# BitRegister.net
KiCad netlist of a schematic drawn in EAGLE
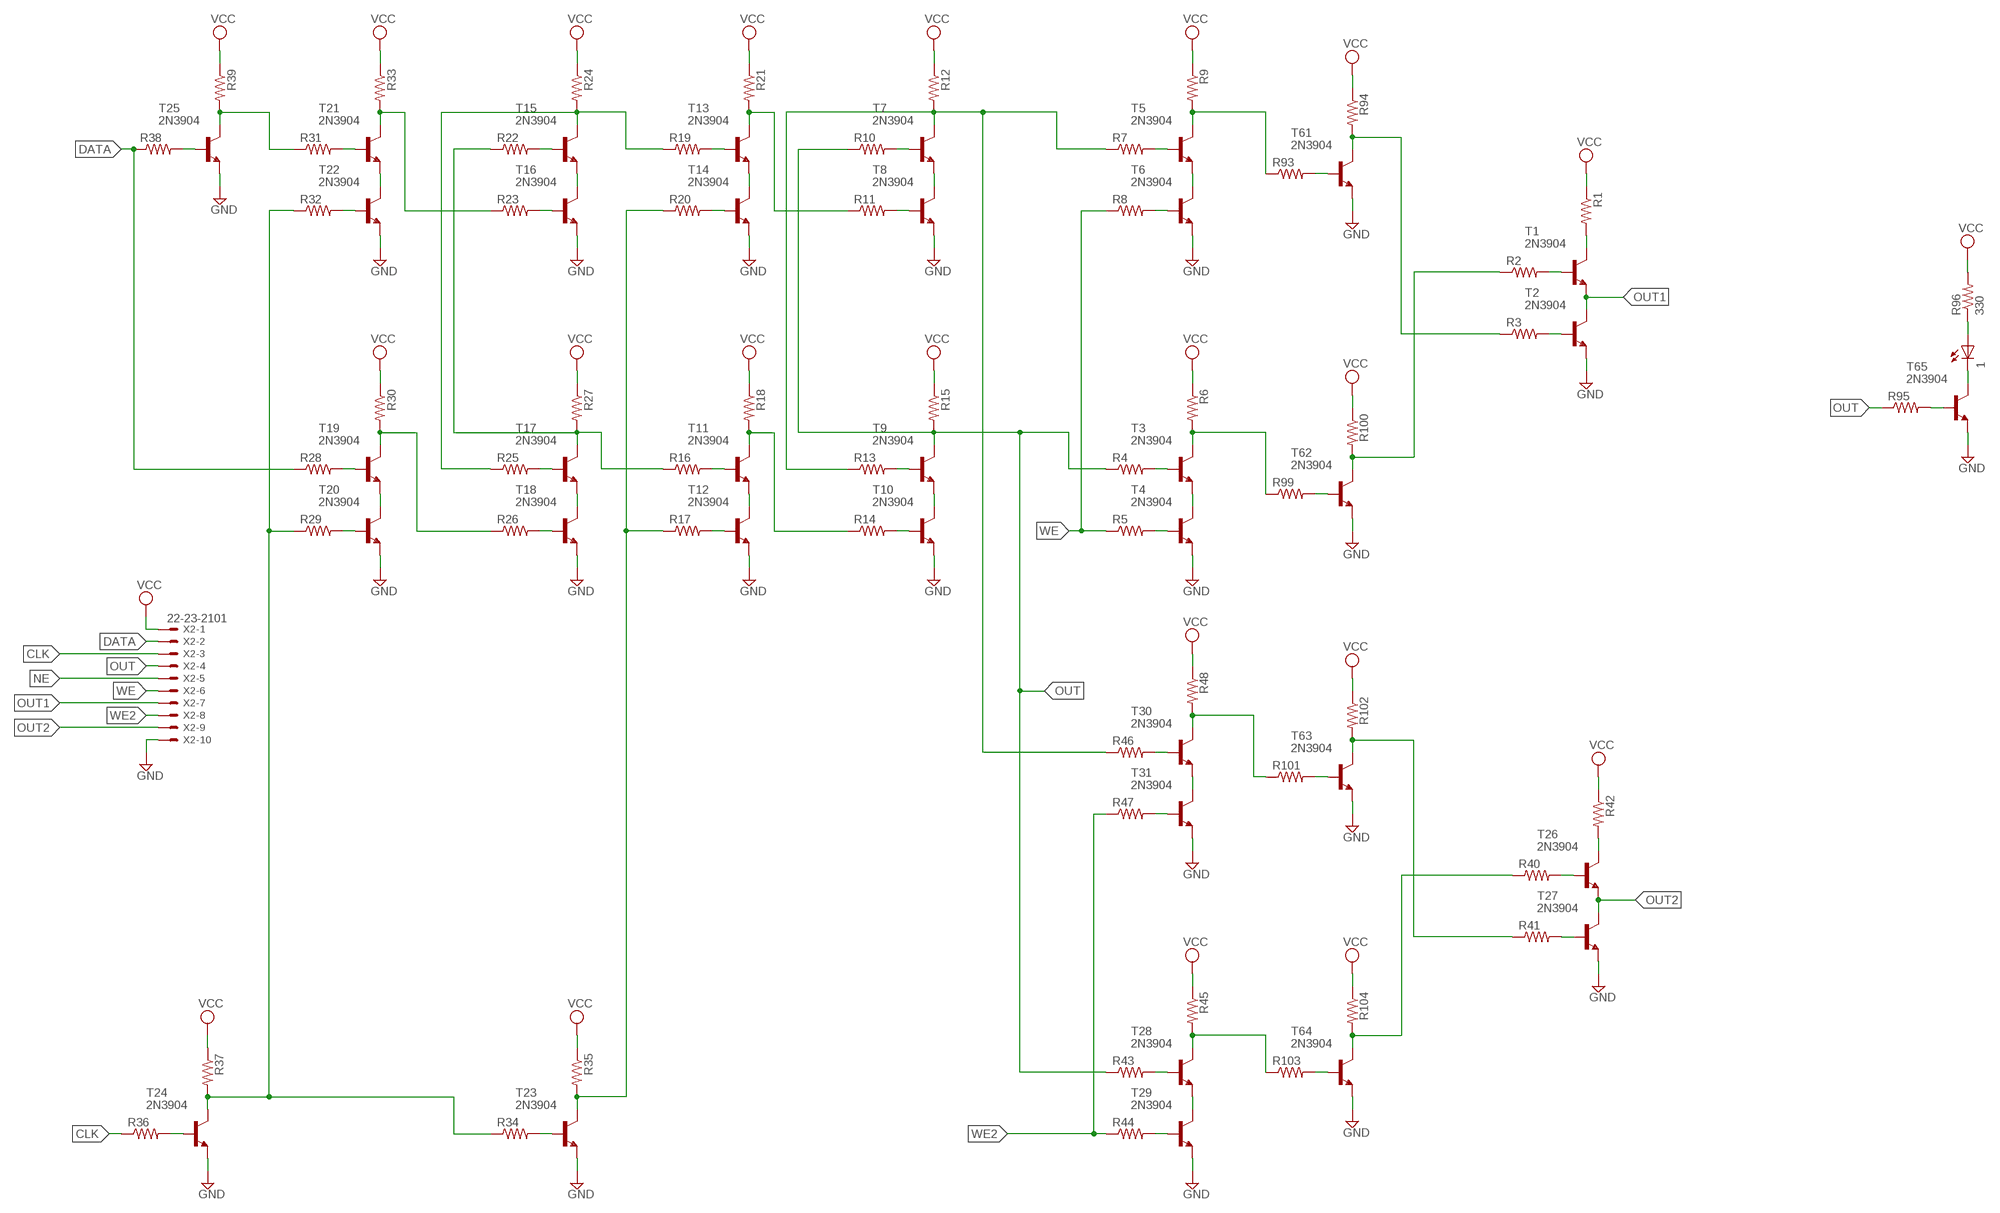
[diagram p0: schematic, sheet 1]

(export (version "E")
  (design (tool "Eeschema 10.0.6"))
  (components
    (comp (ref "1")
      (value "LED5MM")
      (footprint "eagle-import:LED5MM")
      (libsource (lib "eagle-import") (part "LED5MM"))
    )
    (comp (ref "R1")
      (value "R-US_0309/10")
      (footprint "eagle-import:0309_10")
      (libsource (lib "eagle-import") (part "R-US_0309/10"))
    )
    (comp (ref "R2")
      (value "R-US_0309/10")
      (footprint "eagle-import:0309_10")
      (libsource (lib "eagle-import") (part "R-US_0309/10"))
    )
    (comp (ref "R3")
      (value "R-US_0309/10")
      (footprint "eagle-import:0309_10")
      (libsource (lib "eagle-import") (part "R-US_0309/10"))
    )
    (comp (ref "R4")
      (value "R-US_0309/10")
      (footprint "eagle-import:0309_10")
      (libsource (lib "eagle-import") (part "R-US_0309/10"))
    )
    (comp (ref "R5")
      (value "R-US_0309/10")
      (footprint "eagle-import:0309_10")
      (libsource (lib "eagle-import") (part "R-US_0309/10"))
    )
    (comp (ref "R6")
      (value "R-US_0309/10")
      (footprint "eagle-import:0309_10")
      (libsource (lib "eagle-import") (part "R-US_0309/10"))
    )
    (comp (ref "R7")
      (value "R-US_0309/10")
      (footprint "eagle-import:0309_10")
      (libsource (lib "eagle-import") (part "R-US_0309/10"))
    )
    (comp (ref "R8")
      (value "R-US_0309/10")
      (footprint "eagle-import:0309_10")
      (libsource (lib "eagle-import") (part "R-US_0309/10"))
    )
    (comp (ref "R9")
      (value "R-US_0309/10")
      (footprint "eagle-import:0309_10")
      (libsource (lib "eagle-import") (part "R-US_0309/10"))
    )
    (comp (ref "R10")
      (value "R-US_0309/10")
      (footprint "eagle-import:0309_10")
      (libsource (lib "eagle-import") (part "R-US_0309/10"))
    )
    (comp (ref "R11")
      (value "R-US_0309/10")
      (footprint "eagle-import:0309_10")
      (libsource (lib "eagle-import") (part "R-US_0309/10"))
    )
    (comp (ref "R12")
      (value "R-US_0309/10")
      (footprint "eagle-import:0309_10")
      (libsource (lib "eagle-import") (part "R-US_0309/10"))
    )
    (comp (ref "R13")
      (value "R-US_0309/10")
      (footprint "eagle-import:0309_10")
      (libsource (lib "eagle-import") (part "R-US_0309/10"))
    )
    (comp (ref "R14")
      (value "R-US_0309/10")
      (footprint "eagle-import:0309_10")
      (libsource (lib "eagle-import") (part "R-US_0309/10"))
    )
    (comp (ref "R15")
      (value "R-US_0309/10")
      (footprint "eagle-import:0309_10")
      (libsource (lib "eagle-import") (part "R-US_0309/10"))
    )
    (comp (ref "R16")
      (value "R-US_0309/10")
      (footprint "eagle-import:0309_10")
      (libsource (lib "eagle-import") (part "R-US_0309/10"))
    )
    (comp (ref "R17")
      (value "R-US_0309/10")
      (footprint "eagle-import:0309_10")
      (libsource (lib "eagle-import") (part "R-US_0309/10"))
    )
    (comp (ref "R18")
      (value "R-US_0309/10")
      (footprint "eagle-import:0309_10")
      (libsource (lib "eagle-import") (part "R-US_0309/10"))
    )
    (comp (ref "R19")
      (value "R-US_0309/10")
      (footprint "eagle-import:0309_10")
      (libsource (lib "eagle-import") (part "R-US_0309/10"))
    )
    (comp (ref "R20")
      (value "R-US_0309/10")
      (footprint "eagle-import:0309_10")
      (libsource (lib "eagle-import") (part "R-US_0309/10"))
    )
    (comp (ref "R21")
      (value "R-US_0309/10")
      (footprint "eagle-import:0309_10")
      (libsource (lib "eagle-import") (part "R-US_0309/10"))
    )
    (comp (ref "R22")
      (value "R-US_0309/10")
      (footprint "eagle-import:0309_10")
      (libsource (lib "eagle-import") (part "R-US_0309/10"))
    )
    (comp (ref "R23")
      (value "R-US_0309/10")
      (footprint "eagle-import:0309_10")
      (libsource (lib "eagle-import") (part "R-US_0309/10"))
    )
    (comp (ref "R24")
      (value "R-US_0309/10")
      (footprint "eagle-import:0309_10")
      (libsource (lib "eagle-import") (part "R-US_0309/10"))
    )
    (comp (ref "R25")
      (value "R-US_0309/10")
      (footprint "eagle-import:0309_10")
      (libsource (lib "eagle-import") (part "R-US_0309/10"))
    )
    (comp (ref "R26")
      (value "R-US_0309/10")
      (footprint "eagle-import:0309_10")
      (libsource (lib "eagle-import") (part "R-US_0309/10"))
    )
    (comp (ref "R27")
      (value "R-US_0309/10")
      (footprint "eagle-import:0309_10")
      (libsource (lib "eagle-import") (part "R-US_0309/10"))
    )
    (comp (ref "R28")
      (value "R-US_0309/10")
      (footprint "eagle-import:0309_10")
      (libsource (lib "eagle-import") (part "R-US_0309/10"))
    )
    (comp (ref "R29")
      (value "R-US_0309/10")
      (footprint "eagle-import:0309_10")
      (libsource (lib "eagle-import") (part "R-US_0309/10"))
    )
    (comp (ref "R30")
      (value "R-US_0309/10")
      (footprint "eagle-import:0309_10")
      (libsource (lib "eagle-import") (part "R-US_0309/10"))
    )
    (comp (ref "R31")
      (value "R-US_0309/10")
      (footprint "eagle-import:0309_10")
      (libsource (lib "eagle-import") (part "R-US_0309/10"))
    )
    (comp (ref "R32")
      (value "R-US_0309/10")
      (footprint "eagle-import:0309_10")
      (libsource (lib "eagle-import") (part "R-US_0309/10"))
    )
    (comp (ref "R33")
      (value "R-US_0309/10")
      (footprint "eagle-import:0309_10")
      (libsource (lib "eagle-import") (part "R-US_0309/10"))
    )
    (comp (ref "R34")
      (value "R-US_0309/10")
      (footprint "eagle-import:0309_10")
      (libsource (lib "eagle-import") (part "R-US_0309/10"))
    )
    (comp (ref "R35")
      (value "R-US_0309/10")
      (footprint "eagle-import:0309_10")
      (libsource (lib "eagle-import") (part "R-US_0309/10"))
    )
    (comp (ref "R36")
      (value "R-US_0309/10")
      (footprint "eagle-import:0309_10")
      (libsource (lib "eagle-import") (part "R-US_0309/10"))
    )
    (comp (ref "R37")
      (value "R-US_0309/10")
      (footprint "eagle-import:0309_10")
      (libsource (lib "eagle-import") (part "R-US_0309/10"))
    )
    (comp (ref "R38")
      (value "R-US_0309/10")
      (footprint "eagle-import:0309_10")
      (libsource (lib "eagle-import") (part "R-US_0309/10"))
    )
    (comp (ref "R39")
      (value "R-US_0309/10")
      (footprint "eagle-import:0309_10")
      (libsource (lib "eagle-import") (part "R-US_0309/10"))
    )
    (comp (ref "R40")
      (value "R-US_0309/10")
      (footprint "eagle-import:0309_10")
      (libsource (lib "eagle-import") (part "R-US_0309/10"))
    )
    (comp (ref "R41")
      (value "R-US_0309/10")
      (footprint "eagle-import:0309_10")
      (libsource (lib "eagle-import") (part "R-US_0309/10"))
    )
    (comp (ref "R42")
      (value "R-US_0309/10")
      (footprint "eagle-import:0309_10")
      (libsource (lib "eagle-import") (part "R-US_0309/10"))
    )
    (comp (ref "R43")
      (value "R-US_0309/10")
      (footprint "eagle-import:0309_10")
      (libsource (lib "eagle-import") (part "R-US_0309/10"))
    )
    (comp (ref "R44")
      (value "R-US_0309/10")
      (footprint "eagle-import:0309_10")
      (libsource (lib "eagle-import") (part "R-US_0309/10"))
    )
    (comp (ref "R45")
      (value "R-US_0309/10")
      (footprint "eagle-import:0309_10")
      (libsource (lib "eagle-import") (part "R-US_0309/10"))
    )
    (comp (ref "R46")
      (value "R-US_0309/10")
      (footprint "eagle-import:0309_10")
      (libsource (lib "eagle-import") (part "R-US_0309/10"))
    )
    (comp (ref "R47")
      (value "R-US_0309/10")
      (footprint "eagle-import:0309_10")
      (libsource (lib "eagle-import") (part "R-US_0309/10"))
    )
    (comp (ref "R48")
      (value "R-US_0309/10")
      (footprint "eagle-import:0309_10")
      (libsource (lib "eagle-import") (part "R-US_0309/10"))
    )
    (comp (ref "R93")
      (value "R-US_0309/10")
      (footprint "eagle-import:0309_10")
      (libsource (lib "eagle-import") (part "R-US_0309/10"))
    )
    (comp (ref "R94")
      (value "R-US_0309/10")
      (footprint "eagle-import:0309_10")
      (libsource (lib "eagle-import") (part "R-US_0309/10"))
    )
    (comp (ref "R95")
      (value "R-US_0309/10")
      (footprint "eagle-import:0309_10")
      (libsource (lib "eagle-import") (part "R-US_0309/10"))
    )
    (comp (ref "R96")
      (value "330")
      (footprint "eagle-import:0309_10")
      (libsource (lib "eagle-import") (part "R-US_0309/10"))
    )
    (comp (ref "R99")
      (value "R-US_0309/10")
      (footprint "eagle-import:0309_10")
      (libsource (lib "eagle-import") (part "R-US_0309/10"))
    )
    (comp (ref "R100")
      (value "R-US_0309/10")
      (footprint "eagle-import:0309_10")
      (libsource (lib "eagle-import") (part "R-US_0309/10"))
    )
    (comp (ref "R101")
      (value "R-US_0309/10")
      (footprint "eagle-import:0309_10")
      (libsource (lib "eagle-import") (part "R-US_0309/10"))
    )
    (comp (ref "R102")
      (value "R-US_0309/10")
      (footprint "eagle-import:0309_10")
      (libsource (lib "eagle-import") (part "R-US_0309/10"))
    )
    (comp (ref "R103")
      (value "R-US_0309/10")
      (footprint "eagle-import:0309_10")
      (libsource (lib "eagle-import") (part "R-US_0309/10"))
    )
    (comp (ref "R104")
      (value "R-US_0309/10")
      (footprint "eagle-import:0309_10")
      (libsource (lib "eagle-import") (part "R-US_0309/10"))
    )
    (comp (ref "T1")
      (value "2N3904")
      (footprint "eagle-import:TO92")
      (libsource (lib "eagle-import") (part "2N3904"))
    )
    (comp (ref "T2")
      (value "2N3904")
      (footprint "eagle-import:TO92")
      (libsource (lib "eagle-import") (part "2N3904"))
    )
    (comp (ref "T3")
      (value "2N3904")
      (footprint "eagle-import:TO92")
      (libsource (lib "eagle-import") (part "2N3904"))
    )
    (comp (ref "T4")
      (value "2N3904")
      (footprint "eagle-import:TO92")
      (libsource (lib "eagle-import") (part "2N3904"))
    )
    (comp (ref "T5")
      (value "2N3904")
      (footprint "eagle-import:TO92")
      (libsource (lib "eagle-import") (part "2N3904"))
    )
    (comp (ref "T6")
      (value "2N3904")
      (footprint "eagle-import:TO92")
      (libsource (lib "eagle-import") (part "2N3904"))
    )
    (comp (ref "T7")
      (value "2N3904")
      (footprint "eagle-import:TO92")
      (libsource (lib "eagle-import") (part "2N3904"))
    )
    (comp (ref "T8")
      (value "2N3904")
      (footprint "eagle-import:TO92")
      (libsource (lib "eagle-import") (part "2N3904"))
    )
    (comp (ref "T9")
      (value "2N3904")
      (footprint "eagle-import:TO92")
      (libsource (lib "eagle-import") (part "2N3904"))
    )
    (comp (ref "T10")
      (value "2N3904")
      (footprint "eagle-import:TO92")
      (libsource (lib "eagle-import") (part "2N3904"))
    )
    (comp (ref "T11")
      (value "2N3904")
      (footprint "eagle-import:TO92")
      (libsource (lib "eagle-import") (part "2N3904"))
    )
    (comp (ref "T12")
      (value "2N3904")
      (footprint "eagle-import:TO92")
      (libsource (lib "eagle-import") (part "2N3904"))
    )
    (comp (ref "T13")
      (value "2N3904")
      (footprint "eagle-import:TO92")
      (libsource (lib "eagle-import") (part "2N3904"))
    )
    (comp (ref "T14")
      (value "2N3904")
      (footprint "eagle-import:TO92")
      (libsource (lib "eagle-import") (part "2N3904"))
    )
    (comp (ref "T15")
      (value "2N3904")
      (footprint "eagle-import:TO92")
      (libsource (lib "eagle-import") (part "2N3904"))
    )
    (comp (ref "T16")
      (value "2N3904")
      (footprint "eagle-import:TO92")
      (libsource (lib "eagle-import") (part "2N3904"))
    )
    (comp (ref "T17")
      (value "2N3904")
      (footprint "eagle-import:TO92")
      (libsource (lib "eagle-import") (part "2N3904"))
    )
    (comp (ref "T18")
      (value "2N3904")
      (footprint "eagle-import:TO92")
      (libsource (lib "eagle-import") (part "2N3904"))
    )
    (comp (ref "T19")
      (value "2N3904")
      (footprint "eagle-import:TO92")
      (libsource (lib "eagle-import") (part "2N3904"))
    )
    (comp (ref "T20")
      (value "2N3904")
      (footprint "eagle-import:TO92")
      (libsource (lib "eagle-import") (part "2N3904"))
    )
    (comp (ref "T21")
      (value "2N3904")
      (footprint "eagle-import:TO92")
      (libsource (lib "eagle-import") (part "2N3904"))
    )
    (comp (ref "T22")
      (value "2N3904")
      (footprint "eagle-import:TO92")
      (libsource (lib "eagle-import") (part "2N3904"))
    )
    (comp (ref "T23")
      (value "2N3904")
      (footprint "eagle-import:TO92")
      (libsource (lib "eagle-import") (part "2N3904"))
    )
    (comp (ref "T24")
      (value "2N3904")
      (footprint "eagle-import:TO92")
      (libsource (lib "eagle-import") (part "2N3904"))
    )
    (comp (ref "T25")
      (value "2N3904")
      (footprint "eagle-import:TO92")
      (libsource (lib "eagle-import") (part "2N3904"))
    )
    (comp (ref "T26")
      (value "2N3904")
      (footprint "eagle-import:TO92")
      (libsource (lib "eagle-import") (part "2N3904"))
    )
    (comp (ref "T27")
      (value "2N3904")
      (footprint "eagle-import:TO92")
      (libsource (lib "eagle-import") (part "2N3904"))
    )
    (comp (ref "T28")
      (value "2N3904")
      (footprint "eagle-import:TO92")
      (libsource (lib "eagle-import") (part "2N3904"))
    )
    (comp (ref "T29")
      (value "2N3904")
      (footprint "eagle-import:TO92")
      (libsource (lib "eagle-import") (part "2N3904"))
    )
    (comp (ref "T30")
      (value "2N3904")
      (footprint "eagle-import:TO92")
      (libsource (lib "eagle-import") (part "2N3904"))
    )
    (comp (ref "T31")
      (value "2N3904")
      (footprint "eagle-import:TO92")
      (libsource (lib "eagle-import") (part "2N3904"))
    )
    (comp (ref "T61")
      (value "2N3904")
      (footprint "eagle-import:TO92")
      (libsource (lib "eagle-import") (part "2N3904"))
    )
    (comp (ref "T62")
      (value "2N3904")
      (footprint "eagle-import:TO92")
      (libsource (lib "eagle-import") (part "2N3904"))
    )
    (comp (ref "T63")
      (value "2N3904")
      (footprint "eagle-import:TO92")
      (libsource (lib "eagle-import") (part "2N3904"))
    )
    (comp (ref "T64")
      (value "2N3904")
      (footprint "eagle-import:TO92")
      (libsource (lib "eagle-import") (part "2N3904"))
    )
    (comp (ref "T65")
      (value "2N3904")
      (footprint "eagle-import:TO92")
      (libsource (lib "eagle-import") (part "2N3904"))
    )
    (comp (ref "X2")
      (value "22-23-2101")
      (footprint "eagle-import:22-23-2101")
      (fields (field (name "MF") "MOLEX"))
      (libsource (lib "eagle-import") (part "22-23-2101"))
    )
  )
  (nets
    (net (code "1") (name "CLK") (class "Default")
      (node (ref "R36") (pin "1") (pinfunction "1_1") (pintype "passive"))
      (node (ref "X2") (pin "3") (pinfunction "S_3") (pintype "passive"))
    )
    (net (code "2") (name "DATA") (class "Default")
      (node (ref "R28") (pin "1") (pinfunction "1_1") (pintype "passive"))
      (node (ref "R38") (pin "1") (pinfunction "1_1") (pintype "passive"))
      (node (ref "X2") (pin "2") (pinfunction "S_2") (pintype "passive"))
    )
    (net (code "3") (name "GND") (class "Default")
      (node (ref "T10") (pin "3") (pinfunction "E_3") (pintype "passive"))
      (node (ref "T12") (pin "3") (pinfunction "E_3") (pintype "passive"))
      (node (ref "T14") (pin "3") (pinfunction "E_3") (pintype "passive"))
      (node (ref "T16") (pin "3") (pinfunction "E_3") (pintype "passive"))
      (node (ref "T18") (pin "3") (pinfunction "E_3") (pintype "passive"))
      (node (ref "T2") (pin "3") (pinfunction "E_3") (pintype "passive"))
      (node (ref "T20") (pin "3") (pinfunction "E_3") (pintype "passive"))
      (node (ref "T22") (pin "3") (pinfunction "E_3") (pintype "passive"))
      (node (ref "T23") (pin "3") (pinfunction "E_3") (pintype "passive"))
      (node (ref "T24") (pin "3") (pinfunction "E_3") (pintype "passive"))
      (node (ref "T25") (pin "3") (pinfunction "E_3") (pintype "passive"))
      (node (ref "T27") (pin "3") (pinfunction "E_3") (pintype "passive"))
      (node (ref "T29") (pin "3") (pinfunction "E_3") (pintype "passive"))
      (node (ref "T31") (pin "3") (pinfunction "E_3") (pintype "passive"))
      (node (ref "T4") (pin "3") (pinfunction "E_3") (pintype "passive"))
      (node (ref "T6") (pin "3") (pinfunction "E_3") (pintype "passive"))
      (node (ref "T61") (pin "3") (pinfunction "E_3") (pintype "passive"))
      (node (ref "T62") (pin "3") (pinfunction "E_3") (pintype "passive"))
      (node (ref "T63") (pin "3") (pinfunction "E_3") (pintype "passive"))
      (node (ref "T64") (pin "3") (pinfunction "E_3") (pintype "passive"))
      (node (ref "T65") (pin "3") (pinfunction "E_3") (pintype "passive"))
      (node (ref "T8") (pin "3") (pinfunction "E_3") (pintype "passive"))
      (node (ref "X2") (pin "10") (pinfunction "S_10") (pintype "passive"))
    )
    (net (code "4") (name "NE") (class "Default")
      (node (ref "X2") (pin "5") (pinfunction "S_5") (pintype "passive"))
    )
    (net (code "5") (name "Net-(1-C)") (class "Default")
      (node (ref "1") (pin "K") (pinfunction "C_K") (pintype "passive"))
      (node (ref "T65") (pin "1") (pinfunction "C_1") (pintype "passive"))
    )
    (net (code "6") (name "Net-(1-PadA)") (class "Default")
      (node (ref "1") (pin "A") (pinfunction "A_A") (pintype "passive"))
      (node (ref "R96") (pin "1") (pinfunction "1_1") (pintype "passive"))
    )
    (net (code "7") (name "Net-(T1-B)") (class "Default")
      (node (ref "R2") (pin "2") (pinfunction "2_2") (pintype "passive"))
      (node (ref "T1") (pin "2") (pinfunction "B_2") (pintype "passive"))
    )
    (net (code "8") (name "Net-(T1-C)") (class "Default")
      (node (ref "R1") (pin "2") (pinfunction "2_2") (pintype "passive"))
      (node (ref "T1") (pin "1") (pinfunction "C_1") (pintype "passive"))
    )
    (net (code "9") (name "Net-(T2-B)") (class "Default")
      (node (ref "R3") (pin "2") (pinfunction "2_2") (pintype "passive"))
      (node (ref "T2") (pin "2") (pinfunction "B_2") (pintype "passive"))
    )
    (net (code "10") (name "Net-(T3-B)") (class "Default")
      (node (ref "R4") (pin "2") (pinfunction "2_2") (pintype "passive"))
      (node (ref "T3") (pin "2") (pinfunction "B_2") (pintype "passive"))
    )
    (net (code "11") (name "Net-(T3-C)") (class "Default")
      (node (ref "R6") (pin "2") (pinfunction "2_2") (pintype "passive"))
      (node (ref "R99") (pin "1") (pinfunction "1_1") (pintype "passive"))
      (node (ref "T3") (pin "1") (pinfunction "C_1") (pintype "passive"))
    )
    (net (code "12") (name "Net-(T3-E)") (class "Default")
      (node (ref "T3") (pin "3") (pinfunction "E_3") (pintype "passive"))
      (node (ref "T4") (pin "1") (pinfunction "C_1") (pintype "passive"))
    )
    (net (code "13") (name "Net-(T4-B)") (class "Default")
      (node (ref "R5") (pin "2") (pinfunction "2_2") (pintype "passive"))
      (node (ref "T4") (pin "2") (pinfunction "B_2") (pintype "passive"))
    )
    (net (code "14") (name "Net-(T5-B)") (class "Default")
      (node (ref "R7") (pin "2") (pinfunction "2_2") (pintype "passive"))
      (node (ref "T5") (pin "2") (pinfunction "B_2") (pintype "passive"))
    )
    (net (code "15") (name "Net-(T5-C)") (class "Default")
      (node (ref "R9") (pin "2") (pinfunction "2_2") (pintype "passive"))
      (node (ref "R93") (pin "1") (pinfunction "1_1") (pintype "passive"))
      (node (ref "T5") (pin "1") (pinfunction "C_1") (pintype "passive"))
    )
    (net (code "16") (name "Net-(T5-E)") (class "Default")
      (node (ref "T5") (pin "3") (pinfunction "E_3") (pintype "passive"))
      (node (ref "T6") (pin "1") (pinfunction "C_1") (pintype "passive"))
    )
    (net (code "17") (name "Net-(T6-B)") (class "Default")
      (node (ref "R8") (pin "2") (pinfunction "2_2") (pintype "passive"))
      (node (ref "T6") (pin "2") (pinfunction "B_2") (pintype "passive"))
    )
    (net (code "18") (name "Net-(T7-B)") (class "Default")
      (node (ref "R10") (pin "2") (pinfunction "2_2") (pintype "passive"))
      (node (ref "T7") (pin "2") (pinfunction "B_2") (pintype "passive"))
    )
    (net (code "19") (name "Net-(T7-C)") (class "Default")
      (node (ref "R12") (pin "2") (pinfunction "2_2") (pintype "passive"))
      (node (ref "R13") (pin "1") (pinfunction "1_1") (pintype "passive"))
      (node (ref "R46") (pin "1") (pinfunction "1_1") (pintype "passive"))
      (node (ref "R7") (pin "1") (pinfunction "1_1") (pintype "passive"))
      (node (ref "T7") (pin "1") (pinfunction "C_1") (pintype "passive"))
    )
    (net (code "20") (name "Net-(T7-E)") (class "Default")
      (node (ref "T7") (pin "3") (pinfunction "E_3") (pintype "passive"))
      (node (ref "T8") (pin "1") (pinfunction "C_1") (pintype "passive"))
    )
    (net (code "21") (name "Net-(T8-B)") (class "Default")
      (node (ref "R11") (pin "2") (pinfunction "2_2") (pintype "passive"))
      (node (ref "T8") (pin "2") (pinfunction "B_2") (pintype "passive"))
    )
    (net (code "22") (name "Net-(T9-B)") (class "Default")
      (node (ref "R13") (pin "2") (pinfunction "2_2") (pintype "passive"))
      (node (ref "T9") (pin "2") (pinfunction "B_2") (pintype "passive"))
    )
    (net (code "23") (name "Net-(T10-B)") (class "Default")
      (node (ref "R14") (pin "2") (pinfunction "2_2") (pintype "passive"))
      (node (ref "T10") (pin "2") (pinfunction "B_2") (pintype "passive"))
    )
    (net (code "24") (name "Net-(T10-C)") (class "Default")
      (node (ref "T10") (pin "1") (pinfunction "C_1") (pintype "passive"))
      (node (ref "T9") (pin "3") (pinfunction "E_3") (pintype "passive"))
    )
    (net (code "25") (name "Net-(T11-B)") (class "Default")
      (node (ref "R16") (pin "2") (pinfunction "2_2") (pintype "passive"))
      (node (ref "T11") (pin "2") (pinfunction "B_2") (pintype "passive"))
    )
    (net (code "26") (name "Net-(T11-C)") (class "Default")
      (node (ref "R14") (pin "1") (pinfunction "1_1") (pintype "passive"))
      (node (ref "R18") (pin "2") (pinfunction "2_2") (pintype "passive"))
      (node (ref "T11") (pin "1") (pinfunction "C_1") (pintype "passive"))
    )
    (net (code "27") (name "Net-(T11-E)") (class "Default")
      (node (ref "T11") (pin "3") (pinfunction "E_3") (pintype "passive"))
      (node (ref "T12") (pin "1") (pinfunction "C_1") (pintype "passive"))
    )
    (net (code "28") (name "Net-(T12-B)") (class "Default")
      (node (ref "R17") (pin "2") (pinfunction "2_2") (pintype "passive"))
      (node (ref "T12") (pin "2") (pinfunction "B_2") (pintype "passive"))
    )
    (net (code "29") (name "Net-(T13-B)") (class "Default")
      (node (ref "R19") (pin "2") (pinfunction "2_2") (pintype "passive"))
      (node (ref "T13") (pin "2") (pinfunction "B_2") (pintype "passive"))
    )
    (net (code "30") (name "Net-(T13-C)") (class "Default")
      (node (ref "R11") (pin "1") (pinfunction "1_1") (pintype "passive"))
      (node (ref "R21") (pin "2") (pinfunction "2_2") (pintype "passive"))
      (node (ref "T13") (pin "1") (pinfunction "C_1") (pintype "passive"))
    )
    (net (code "31") (name "Net-(T13-E)") (class "Default")
      (node (ref "T13") (pin "3") (pinfunction "E_3") (pintype "passive"))
      (node (ref "T14") (pin "1") (pinfunction "C_1") (pintype "passive"))
    )
    (net (code "32") (name "Net-(T14-B)") (class "Default")
      (node (ref "R20") (pin "2") (pinfunction "2_2") (pintype "passive"))
      (node (ref "T14") (pin "2") (pinfunction "B_2") (pintype "passive"))
    )
    (net (code "33") (name "Net-(T15-B)") (class "Default")
      (node (ref "R22") (pin "2") (pinfunction "2_2") (pintype "passive"))
      (node (ref "T15") (pin "2") (pinfunction "B_2") (pintype "passive"))
    )
    (net (code "34") (name "Net-(T15-C)") (class "Default")
      (node (ref "R19") (pin "1") (pinfunction "1_1") (pintype "passive"))
      (node (ref "R24") (pin "2") (pinfunction "2_2") (pintype "passive"))
      (node (ref "R25") (pin "1") (pinfunction "1_1") (pintype "passive"))
      (node (ref "T15") (pin "1") (pinfunction "C_1") (pintype "passive"))
    )
    (net (code "35") (name "Net-(T15-E)") (class "Default")
      (node (ref "T15") (pin "3") (pinfunction "E_3") (pintype "passive"))
      (node (ref "T16") (pin "1") (pinfunction "C_1") (pintype "passive"))
    )
    (net (code "36") (name "Net-(T16-B)") (class "Default")
      (node (ref "R23") (pin "2") (pinfunction "2_2") (pintype "passive"))
      (node (ref "T16") (pin "2") (pinfunction "B_2") (pintype "passive"))
    )
    (net (code "37") (name "Net-(T17-B)") (class "Default")
      (node (ref "R25") (pin "2") (pinfunction "2_2") (pintype "passive"))
      (node (ref "T17") (pin "2") (pinfunction "B_2") (pintype "passive"))
    )
    (net (code "38") (name "Net-(T17-C)") (class "Default")
      (node (ref "R16") (pin "1") (pinfunction "1_1") (pintype "passive"))
      (node (ref "R22") (pin "1") (pinfunction "1_1") (pintype "passive"))
      (node (ref "R27") (pin "2") (pinfunction "2_2") (pintype "passive"))
      (node (ref "T17") (pin "1") (pinfunction "C_1") (pintype "passive"))
    )
    (net (code "39") (name "Net-(T17-E)") (class "Default")
      (node (ref "T17") (pin "3") (pinfunction "E_3") (pintype "passive"))
      (node (ref "T18") (pin "1") (pinfunction "C_1") (pintype "passive"))
    )
    (net (code "40") (name "Net-(T18-B)") (class "Default")
      (node (ref "R26") (pin "2") (pinfunction "2_2") (pintype "passive"))
      (node (ref "T18") (pin "2") (pinfunction "B_2") (pintype "passive"))
    )
    (net (code "41") (name "Net-(T19-B)") (class "Default")
      (node (ref "R28") (pin "2") (pinfunction "2_2") (pintype "passive"))
      (node (ref "T19") (pin "2") (pinfunction "B_2") (pintype "passive"))
    )
    (net (code "42") (name "Net-(T19-C)") (class "Default")
      (node (ref "R26") (pin "1") (pinfunction "1_1") (pintype "passive"))
      (node (ref "R30") (pin "2") (pinfunction "2_2") (pintype "passive"))
      (node (ref "T19") (pin "1") (pinfunction "C_1") (pintype "passive"))
    )
    (net (code "43") (name "Net-(T19-E)") (class "Default")
      (node (ref "T19") (pin "3") (pinfunction "E_3") (pintype "passive"))
      (node (ref "T20") (pin "1") (pinfunction "C_1") (pintype "passive"))
    )
    (net (code "44") (name "Net-(T20-B)") (class "Default")
      (node (ref "R29") (pin "2") (pinfunction "2_2") (pintype "passive"))
      (node (ref "T20") (pin "2") (pinfunction "B_2") (pintype "passive"))
    )
    (net (code "45") (name "Net-(T21-B)") (class "Default")
      (node (ref "R31") (pin "2") (pinfunction "2_2") (pintype "passive"))
      (node (ref "T21") (pin "2") (pinfunction "B_2") (pintype "passive"))
    )
    (net (code "46") (name "Net-(T21-C)") (class "Default")
      (node (ref "R23") (pin "1") (pinfunction "1_1") (pintype "passive"))
      (node (ref "R33") (pin "2") (pinfunction "2_2") (pintype "passive"))
      (node (ref "T21") (pin "1") (pinfunction "C_1") (pintype "passive"))
    )
    (net (code "47") (name "Net-(T21-E)") (class "Default")
      (node (ref "T21") (pin "3") (pinfunction "E_3") (pintype "passive"))
      (node (ref "T22") (pin "1") (pinfunction "C_1") (pintype "passive"))
    )
    (net (code "48") (name "Net-(T22-B)") (class "Default")
      (node (ref "R32") (pin "2") (pinfunction "2_2") (pintype "passive"))
      (node (ref "T22") (pin "2") (pinfunction "B_2") (pintype "passive"))
    )
    (net (code "49") (name "Net-(T23-B)") (class "Default")
      (node (ref "R34") (pin "2") (pinfunction "2_2") (pintype "passive"))
      (node (ref "T23") (pin "2") (pinfunction "B_2") (pintype "passive"))
    )
    (net (code "50") (name "Net-(T23-C)") (class "Default")
      (node (ref "R17") (pin "1") (pinfunction "1_1") (pintype "passive"))
      (node (ref "R20") (pin "1") (pinfunction "1_1") (pintype "passive"))
      (node (ref "R35") (pin "2") (pinfunction "2_2") (pintype "passive"))
      (node (ref "T23") (pin "1") (pinfunction "C_1") (pintype "passive"))
    )
    (net (code "51") (name "Net-(T24-B)") (class "Default")
      (node (ref "R36") (pin "2") (pinfunction "2_2") (pintype "passive"))
      (node (ref "T24") (pin "2") (pinfunction "B_2") (pintype "passive"))
    )
    (net (code "52") (name "Net-(T24-C)") (class "Default")
      (node (ref "R29") (pin "1") (pinfunction "1_1") (pintype "passive"))
      (node (ref "R32") (pin "1") (pinfunction "1_1") (pintype "passive"))
      (node (ref "R34") (pin "1") (pinfunction "1_1") (pintype "passive"))
      (node (ref "R37") (pin "2") (pinfunction "2_2") (pintype "passive"))
      (node (ref "T24") (pin "1") (pinfunction "C_1") (pintype "passive"))
    )
    (net (code "53") (name "Net-(T25-B)") (class "Default")
      (node (ref "R38") (pin "2") (pinfunction "2_2") (pintype "passive"))
      (node (ref "T25") (pin "2") (pinfunction "B_2") (pintype "passive"))
    )
    (net (code "54") (name "Net-(T25-C)") (class "Default")
      (node (ref "R31") (pin "1") (pinfunction "1_1") (pintype "passive"))
      (node (ref "R39") (pin "2") (pinfunction "2_2") (pintype "passive"))
      (node (ref "T25") (pin "1") (pinfunction "C_1") (pintype "passive"))
    )
    (net (code "55") (name "Net-(T26-B)") (class "Default")
      (node (ref "R40") (pin "2") (pinfunction "2_2") (pintype "passive"))
      (node (ref "T26") (pin "2") (pinfunction "B_2") (pintype "passive"))
    )
    (net (code "56") (name "Net-(T26-C)") (class "Default")
      (node (ref "R42") (pin "2") (pinfunction "2_2") (pintype "passive"))
      (node (ref "T26") (pin "1") (pinfunction "C_1") (pintype "passive"))
    )
    (net (code "57") (name "Net-(T27-B)") (class "Default")
      (node (ref "R41") (pin "2") (pinfunction "2_2") (pintype "passive"))
      (node (ref "T27") (pin "2") (pinfunction "B_2") (pintype "passive"))
    )
    (net (code "58") (name "Net-(T28-B)") (class "Default")
      (node (ref "R43") (pin "2") (pinfunction "2_2") (pintype "passive"))
      (node (ref "T28") (pin "2") (pinfunction "B_2") (pintype "passive"))
    )
    (net (code "59") (name "Net-(T28-C)") (class "Default")
      (node (ref "R103") (pin "1") (pinfunction "1_1") (pintype "passive"))
      (node (ref "R45") (pin "2") (pinfunction "2_2") (pintype "passive"))
      (node (ref "T28") (pin "1") (pinfunction "C_1") (pintype "passive"))
    )
    (net (code "60") (name "Net-(T28-E)") (class "Default")
      (node (ref "T28") (pin "3") (pinfunction "E_3") (pintype "passive"))
      (node (ref "T29") (pin "1") (pinfunction "C_1") (pintype "passive"))
    )
    (net (code "61") (name "Net-(T29-B)") (class "Default")
      (node (ref "R44") (pin "2") (pinfunction "2_2") (pintype "passive"))
      (node (ref "T29") (pin "2") (pinfunction "B_2") (pintype "passive"))
    )
    (net (code "62") (name "Net-(T30-B)") (class "Default")
      (node (ref "R46") (pin "2") (pinfunction "2_2") (pintype "passive"))
      (node (ref "T30") (pin "2") (pinfunction "B_2") (pintype "passive"))
    )
    (net (code "63") (name "Net-(T30-C)") (class "Default")
      (node (ref "R101") (pin "1") (pinfunction "1_1") (pintype "passive"))
      (node (ref "R48") (pin "2") (pinfunction "2_2") (pintype "passive"))
      (node (ref "T30") (pin "1") (pinfunction "C_1") (pintype "passive"))
    )
    (net (code "64") (name "Net-(T30-E)") (class "Default")
      (node (ref "T30") (pin "3") (pinfunction "E_3") (pintype "passive"))
      (node (ref "T31") (pin "1") (pinfunction "C_1") (pintype "passive"))
    )
    (net (code "65") (name "Net-(T31-B)") (class "Default")
      (node (ref "R47") (pin "2") (pinfunction "2_2") (pintype "passive"))
      (node (ref "T31") (pin "2") (pinfunction "B_2") (pintype "passive"))
    )
    (net (code "66") (name "Net-(T61-B)") (class "Default")
      (node (ref "R93") (pin "2") (pinfunction "2_2") (pintype "passive"))
      (node (ref "T61") (pin "2") (pinfunction "B_2") (pintype "passive"))
    )
    (net (code "67") (name "Net-(T61-C)") (class "Default")
      (node (ref "R3") (pin "1") (pinfunction "1_1") (pintype "passive"))
      (node (ref "R94") (pin "2") (pinfunction "2_2") (pintype "passive"))
      (node (ref "T61") (pin "1") (pinfunction "C_1") (pintype "passive"))
    )
    (net (code "68") (name "Net-(T62-B)") (class "Default")
      (node (ref "R99") (pin "2") (pinfunction "2_2") (pintype "passive"))
      (node (ref "T62") (pin "2") (pinfunction "B_2") (pintype "passive"))
    )
    (net (code "69") (name "Net-(T62-C)") (class "Default")
      (node (ref "R100") (pin "2") (pinfunction "2_2") (pintype "passive"))
      (node (ref "R2") (pin "1") (pinfunction "1_1") (pintype "passive"))
      (node (ref "T62") (pin "1") (pinfunction "C_1") (pintype "passive"))
    )
    (net (code "70") (name "Net-(T63-B)") (class "Default")
      (node (ref "R101") (pin "2") (pinfunction "2_2") (pintype "passive"))
      (node (ref "T63") (pin "2") (pinfunction "B_2") (pintype "passive"))
    )
    (net (code "71") (name "Net-(T63-C)") (class "Default")
      (node (ref "R102") (pin "2") (pinfunction "2_2") (pintype "passive"))
      (node (ref "R41") (pin "1") (pinfunction "1_1") (pintype "passive"))
      (node (ref "T63") (pin "1") (pinfunction "C_1") (pintype "passive"))
    )
    (net (code "72") (name "Net-(T64-B)") (class "Default")
      (node (ref "R103") (pin "2") (pinfunction "2_2") (pintype "passive"))
      (node (ref "T64") (pin "2") (pinfunction "B_2") (pintype "passive"))
    )
    (net (code "73") (name "Net-(T64-C)") (class "Default")
      (node (ref "R104") (pin "2") (pinfunction "2_2") (pintype "passive"))
      (node (ref "R40") (pin "1") (pinfunction "1_1") (pintype "passive"))
      (node (ref "T64") (pin "1") (pinfunction "C_1") (pintype "passive"))
    )
    (net (code "74") (name "Net-(T65-B)") (class "Default")
      (node (ref "R95") (pin "2") (pinfunction "2_2") (pintype "passive"))
      (node (ref "T65") (pin "2") (pinfunction "B_2") (pintype "passive"))
    )
    (net (code "75") (name "OUT") (class "Default")
      (node (ref "R10") (pin "1") (pinfunction "1_1") (pintype "passive"))
      (node (ref "R15") (pin "2") (pinfunction "2_2") (pintype "passive"))
      (node (ref "R4") (pin "1") (pinfunction "1_1") (pintype "passive"))
      (node (ref "R43") (pin "1") (pinfunction "1_1") (pintype "passive"))
      (node (ref "R95") (pin "1") (pinfunction "1_1") (pintype "passive"))
      (node (ref "T9") (pin "1") (pinfunction "C_1") (pintype "passive"))
      (node (ref "X2") (pin "4") (pinfunction "S_4") (pintype "passive"))
    )
    (net (code "76") (name "OUT1") (class "Default")
      (node (ref "T1") (pin "3") (pinfunction "E_3") (pintype "passive"))
      (node (ref "T2") (pin "1") (pinfunction "C_1") (pintype "passive"))
      (node (ref "X2") (pin "7") (pinfunction "S_7") (pintype "passive"))
    )
    (net (code "77") (name "OUT2") (class "Default")
      (node (ref "T26") (pin "3") (pinfunction "E_3") (pintype "passive"))
      (node (ref "T27") (pin "1") (pinfunction "C_1") (pintype "passive"))
      (node (ref "X2") (pin "9") (pinfunction "S_9") (pintype "passive"))
    )
    (net (code "78") (name "VCC") (class "Default")
      (node (ref "R1") (pin "1") (pinfunction "1_1") (pintype "passive"))
      (node (ref "R100") (pin "1") (pinfunction "1_1") (pintype "passive"))
      (node (ref "R102") (pin "1") (pinfunction "1_1") (pintype "passive"))
      (node (ref "R104") (pin "1") (pinfunction "1_1") (pintype "passive"))
      (node (ref "R12") (pin "1") (pinfunction "1_1") (pintype "passive"))
      (node (ref "R15") (pin "1") (pinfunction "1_1") (pintype "passive"))
      (node (ref "R18") (pin "1") (pinfunction "1_1") (pintype "passive"))
      (node (ref "R21") (pin "1") (pinfunction "1_1") (pintype "passive"))
      (node (ref "R24") (pin "1") (pinfunction "1_1") (pintype "passive"))
      (node (ref "R27") (pin "1") (pinfunction "1_1") (pintype "passive"))
      (node (ref "R30") (pin "1") (pinfunction "1_1") (pintype "passive"))
      (node (ref "R33") (pin "1") (pinfunction "1_1") (pintype "passive"))
      (node (ref "R35") (pin "1") (pinfunction "1_1") (pintype "passive"))
      (node (ref "R37") (pin "1") (pinfunction "1_1") (pintype "passive"))
      (node (ref "R39") (pin "1") (pinfunction "1_1") (pintype "passive"))
      (node (ref "R42") (pin "1") (pinfunction "1_1") (pintype "passive"))
      (node (ref "R45") (pin "1") (pinfunction "1_1") (pintype "passive"))
      (node (ref "R48") (pin "1") (pinfunction "1_1") (pintype "passive"))
      (node (ref "R6") (pin "1") (pinfunction "1_1") (pintype "passive"))
      (node (ref "R9") (pin "1") (pinfunction "1_1") (pintype "passive"))
      (node (ref "R94") (pin "1") (pinfunction "1_1") (pintype "passive"))
      (node (ref "R96") (pin "2") (pinfunction "2_2") (pintype "passive"))
      (node (ref "X2") (pin "1") (pinfunction "S_1") (pintype "passive"))
    )
    (net (code "79") (name "WE") (class "Default")
      (node (ref "R5") (pin "1") (pinfunction "1_1") (pintype "passive"))
      (node (ref "R8") (pin "1") (pinfunction "1_1") (pintype "passive"))
      (node (ref "X2") (pin "6") (pinfunction "S_6") (pintype "passive"))
    )
    (net (code "80") (name "WE2") (class "Default")
      (node (ref "R44") (pin "1") (pinfunction "1_1") (pintype "passive"))
      (node (ref "R47") (pin "1") (pinfunction "1_1") (pintype "passive"))
      (node (ref "X2") (pin "8") (pinfunction "S_8") (pintype "passive"))
    )
  )
)
